# TopLevel.net
KiCad netlist of a schematic drawn in Altium Designer
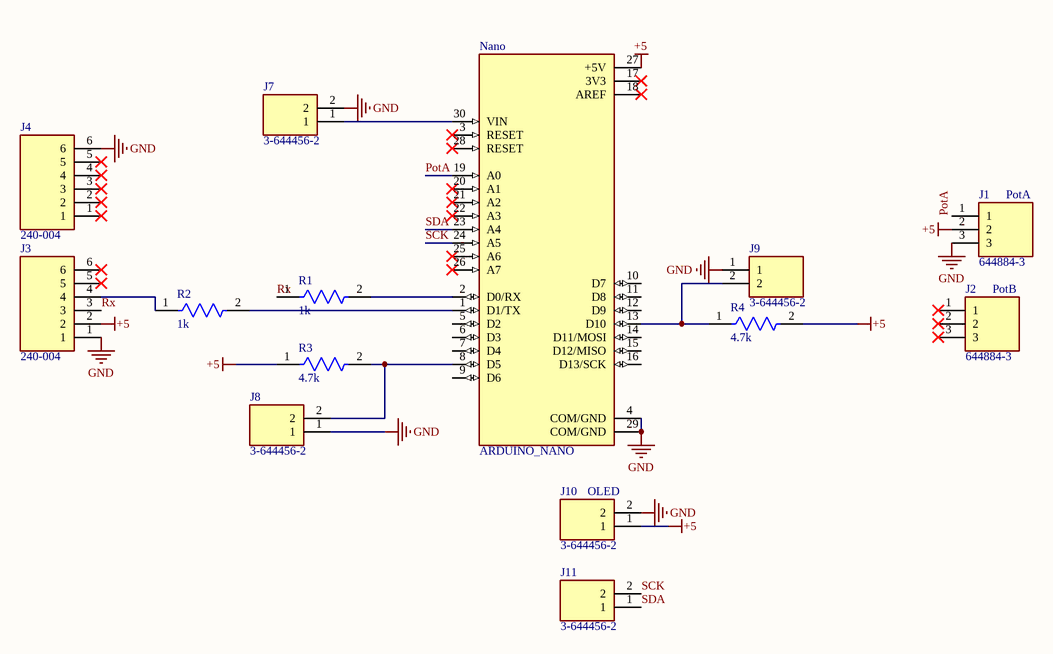
[diagram p0: TopLevel.SchDoc]

(export (version "E")
  (design (tool "Eeschema 10.0.6"))
  (components
    (comp (ref "J1")
      (value "644884-3")
      (footprint "TE_644884-3")
      (libsource (lib "Ryusei Kinosaki") (part "644884-3"))
    )
    (comp (ref "J2")
      (value "644884-3")
      (footprint "TE_644884-3")
      (libsource (lib "Ryusei Kinosaki") (part "644884-3"))
    )
    (comp (ref "J3")
      (value "240-004")
      (footprint "SamacSys:HDRV6W64P0X254_1X6_1524X254X909P")
      (description "Connector")
      (libsource (lib "*") (part "240-004"))
    )
    (comp (ref "J4")
      (value "240-004")
      (footprint "SamacSys:HDRV6W64P0X254_1X6_1524X254X909P")
      (description "Connector")
      (libsource (lib "*") (part "240-004"))
    )
    (comp (ref "J7")
      (value "3-644456-2")
      (footprint "TE_3-644456-2")
      (description "Connector Unshrouded Header HDR 2 Position 2.54mm Solder Straight Thru-Hole")
      (fields (field (name "MF") "TE Connectivity") (field (name "DIGI-KEY_PART_NUMBER") "A31112-ND"))
      (libsource (lib "") (part "3-644456-2_1"))
    )
    (comp (ref "J8")
      (value "3-644456-2")
      (footprint "TE_3-644456-2")
      (description "Connector Unshrouded Header HDR 2 Position 2.54mm Solder Straight Thru-Hole")
      (fields (field (name "MF") "TE Connectivity") (field (name "DIGI-KEY_PART_NUMBER") "A31112-ND"))
      (libsource (lib "") (part "3-644456-2_1"))
    )
    (comp (ref "J9")
      (value "3-644456-2")
      (footprint "TE_3-644456-2")
      (description "Connector Unshrouded Header HDR 2 Position 2.54mm Solder Straight Thru-Hole")
      (fields (field (name "MF") "TE Connectivity") (field (name "DIGI-KEY_PART_NUMBER") "A31112-ND"))
      (libsource (lib "Ryusei Kinosaki") (part "3-644456-2"))
    )
    (comp (ref "J10")
      (value "3-644456-2")
      (footprint "TE_3-644456-2")
      (description "Connector Unshrouded Header HDR 2 Position 2.54mm Solder Straight Thru-Hole")
      (fields (field (name "MF") "TE Connectivity") (field (name "DIGI-KEY_PART_NUMBER") "A31112-ND"))
      (libsource (lib "") (part "3-644456-2_1"))
    )
    (comp (ref "J11")
      (value "3-644456-2")
      (footprint "TE_3-644456-2")
      (description "Connector Unshrouded Header HDR 2 Position 2.54mm Solder Straight Thru-Hole")
      (fields (field (name "MF") "TE Connectivity") (field (name "DIGI-KEY_PART_NUMBER") "A31112-ND"))
      (libsource (lib "") (part "3-644456-2_1"))
    )
    (comp (ref "Nano")
      (value "ARDUINO_NANO")
      (footprint "SHIELD_ARDUINO_NANO")
      (description "Small, complete, and breadboard-friendly board based on the ATmega328 (Arduino Nano 3.x)")
      (fields (field (name "MF") "Arduino") (field (name "MP") "Arduino Nano"))
      (libsource (lib "Ryusei Kinosaki") (part "ARDUINO_NANO"))
    )
    (comp (ref "R1")
      (value "MRS25000C1001FCT00")
      (footprint "FP-MRS25-MFG")
      (description "RES 1K OHM 0.6W 1% AXIAL")
      (fields (field (name "TOLERANCE") "1%") (field (name "RESISTANCE") "1k"))
      (libsource (lib "Altium Content Vault") (part "1029c3af85768c4190bb7ad29bc67b5"))
    )
    (comp (ref "R2")
      (value "MRS25000C1001FCT00")
      (footprint "FP-MRS25-MFG")
      (description "RES 1K OHM 0.6W 1% AXIAL")
      (fields (field (name "TOLERANCE") "1%") (field (name "RESISTANCE") "1k"))
      (libsource (lib "Altium Content Vault") (part "1029c3af85768c4190bb7ad29bc67b5"))
    )
    (comp (ref "R3")
      (value "MRS25000C1001FCT00")
      (footprint "FP-MRS25-MFG")
      (description "RES 1K OHM 0.6W 1% AXIAL")
      (fields (field (name "TOLERANCE") "1%") (field (name "RESISTANCE") "4.7k"))
      (libsource (lib "Altium Content Vault") (part "1029c3af85768c4190bb7ad29bc67b5"))
    )
    (comp (ref "R4")
      (value "MRS25000C1001FCT00")
      (footprint "FP-MRS25-MFG")
      (description "RES 1K OHM 0.6W 1% AXIAL")
      (fields (field (name "TOLERANCE") "1%") (field (name "RESISTANCE") "4.7k"))
      (libsource (lib "Altium Content Vault") (part "1029c3af85768c4190bb7ad29bc67b5"))
    )
  )
  (nets
    (net (code "1") (name "+5") (class "Default")
      (node (ref "J1") (pin "2") (pinfunction "2_2") (pintype "passive"))
      (node (ref "J10") (pin "1") (pinfunction "1_1") (pintype "passive"))
      (node (ref "J3") (pin "2") (pinfunction "2_2") (pintype "passive"))
      (node (ref "Nano") (pin "27") (pinfunction "+5V_27") (pintype "power_in"))
      (node (ref "R3") (pin "1") (pinfunction "1_1") (pintype "passive"))
      (node (ref "R4") (pin "2") (pinfunction "2_2") (pintype "passive"))
    )
    (net (code "2") (name "/PotA") (class "Default")
      (node (ref "J1") (pin "1") (pinfunction "1_1") (pintype "passive"))
      (node (ref "Nano") (pin "19") (pinfunction "A0_19") (pintype "input"))
    )
    (net (code "3") (name "/Rx") (class "Default")
      (node (ref "J3") (pin "3") (pinfunction "3_3") (pintype "passive"))
      (node (ref "R1") (pin "1") (pinfunction "1_1") (pintype "passive"))
    )
    (net (code "4") (name "/SCK") (class "Default")
      (node (ref "J11") (pin "2") (pinfunction "2_2") (pintype "passive"))
      (node (ref "Nano") (pin "24") (pinfunction "A5_24") (pintype "input"))
    )
    (net (code "5") (name "/SDA") (class "Default")
      (node (ref "J11") (pin "1") (pinfunction "1_1") (pintype "passive"))
      (node (ref "Nano") (pin "23") (pinfunction "A4_23") (pintype "input"))
    )
    (net (code "6") (name "GND") (class "Default")
      (node (ref "J1") (pin "3") (pinfunction "3_3") (pintype "passive"))
      (node (ref "J10") (pin "2") (pinfunction "2_2") (pintype "passive"))
      (node (ref "J3") (pin "1") (pinfunction "1_1") (pintype "passive"))
      (node (ref "J4") (pin "6") (pinfunction "6_6") (pintype "passive"))
      (node (ref "J7") (pin "2") (pinfunction "2_2") (pintype "passive"))
      (node (ref "J8") (pin "1") (pinfunction "1_1") (pintype "passive"))
      (node (ref "J9") (pin "1") (pinfunction "1_1") (pintype "passive"))
      (node (ref "Nano") (pin "29") (pinfunction "COM/GND_29") (pintype "power_in"))
      (node (ref "Nano") (pin "4") (pinfunction "COM/GND_4") (pintype "power_in"))
    )
    (net (code "7") (name "Net-(J3-Pad4)") (class "Default")
      (node (ref "J3") (pin "4") (pinfunction "4_4") (pintype "passive"))
      (node (ref "R2") (pin "1") (pinfunction "1_1") (pintype "passive"))
    )
    (net (code "8") (name "Net-(Nano-D0{slash}RX)") (class "Default")
      (node (ref "Nano") (pin "2") (pinfunction "D0/RX_2") (pintype "bidirectional"))
      (node (ref "R1") (pin "2") (pinfunction "2_2") (pintype "passive"))
    )
    (net (code "9") (name "Net-(Nano-D1{slash}TX)") (class "Default")
      (node (ref "Nano") (pin "1") (pinfunction "D1/TX_1") (pintype "bidirectional"))
      (node (ref "R2") (pin "2") (pinfunction "2_2") (pintype "passive"))
    )
    (net (code "10") (name "Net-(Nano-D5)") (class "Default")
      (node (ref "J8") (pin "2") (pinfunction "2_2") (pintype "passive"))
      (node (ref "Nano") (pin "8") (pinfunction "D5_8") (pintype "bidirectional"))
      (node (ref "R3") (pin "2") (pinfunction "2_2") (pintype "passive"))
    )
    (net (code "11") (name "Net-(Nano-D10)") (class "Default")
      (node (ref "J9") (pin "2") (pinfunction "2_2") (pintype "passive"))
      (node (ref "Nano") (pin "13") (pinfunction "D10_13") (pintype "bidirectional"))
      (node (ref "R4") (pin "1") (pinfunction "1_1") (pintype "passive"))
    )
    (net (code "12") (name "Net-(Nano-VIN)") (class "Default")
      (node (ref "J7") (pin "1") (pinfunction "1_1") (pintype "passive"))
      (node (ref "Nano") (pin "30") (pinfunction "VIN_30") (pintype "input"))
    )
    (net (code "13") (name "unconnected-(J2-Pad1)") (class "Default")
      (node (ref "J2") (pin "1") (pinfunction "1_1") (pintype "passive+no_connect"))
    )
    (net (code "14") (name "unconnected-(J2-Pad2)") (class "Default")
      (node (ref "J2") (pin "2") (pinfunction "2_2") (pintype "passive+no_connect"))
    )
    (net (code "15") (name "unconnected-(J2-Pad3)") (class "Default")
      (node (ref "J2") (pin "3") (pinfunction "3_3") (pintype "passive+no_connect"))
    )
    (net (code "16") (name "unconnected-(J3-Pad5)") (class "Default")
      (node (ref "J3") (pin "5") (pinfunction "5_5") (pintype "passive+no_connect"))
    )
    (net (code "17") (name "unconnected-(J3-Pad6)") (class "Default")
      (node (ref "J3") (pin "6") (pinfunction "6_6") (pintype "passive+no_connect"))
    )
    (net (code "18") (name "unconnected-(J4-Pad1)") (class "Default")
      (node (ref "J4") (pin "1") (pinfunction "1_1") (pintype "passive+no_connect"))
    )
    (net (code "19") (name "unconnected-(J4-Pad2)") (class "Default")
      (node (ref "J4") (pin "2") (pinfunction "2_2") (pintype "passive+no_connect"))
    )
    (net (code "20") (name "unconnected-(J4-Pad3)") (class "Default")
      (node (ref "J4") (pin "3") (pinfunction "3_3") (pintype "passive+no_connect"))
    )
    (net (code "21") (name "unconnected-(J4-Pad4)") (class "Default")
      (node (ref "J4") (pin "4") (pinfunction "4_4") (pintype "passive+no_connect"))
    )
    (net (code "22") (name "unconnected-(J4-Pad5)") (class "Default")
      (node (ref "J4") (pin "5") (pinfunction "5_5") (pintype "passive+no_connect"))
    )
    (net (code "23") (name "unconnected-(Nano-3V3-Pad17)") (class "Default")
      (node (ref "Nano") (pin "17") (pinfunction "3V3_17") (pintype "power_in+no_connect"))
    )
    (net (code "24") (name "unconnected-(Nano-A1-Pad20)") (class "Default")
      (node (ref "Nano") (pin "20") (pinfunction "A1_20") (pintype "input+no_connect"))
    )
    (net (code "25") (name "unconnected-(Nano-A2-Pad21)") (class "Default")
      (node (ref "Nano") (pin "21") (pinfunction "A2_21") (pintype "input+no_connect"))
    )
    (net (code "26") (name "unconnected-(Nano-A3-Pad22)") (class "Default")
      (node (ref "Nano") (pin "22") (pinfunction "A3_22") (pintype "input+no_connect"))
    )
    (net (code "27") (name "unconnected-(Nano-A6-Pad25)") (class "Default")
      (node (ref "Nano") (pin "25") (pinfunction "A6_25") (pintype "input+no_connect"))
    )
    (net (code "28") (name "unconnected-(Nano-A7-Pad26)") (class "Default")
      (node (ref "Nano") (pin "26") (pinfunction "A7_26") (pintype "input+no_connect"))
    )
    (net (code "29") (name "unconnected-(Nano-AREF-Pad18)") (class "Default")
      (node (ref "Nano") (pin "18") (pinfunction "AREF_18") (pintype "power_in+no_connect"))
    )
    (net (code "30") (name "unconnected-(Nano-D2-Pad5)") (class "Default")
      (node (ref "Nano") (pin "5") (pinfunction "D2_5") (pintype "bidirectional"))
    )
    (net (code "31") (name "unconnected-(Nano-D3-Pad6)") (class "Default")
      (node (ref "Nano") (pin "6") (pinfunction "D3_6") (pintype "bidirectional"))
    )
    (net (code "32") (name "unconnected-(Nano-D4-Pad7)") (class "Default")
      (node (ref "Nano") (pin "7") (pinfunction "D4_7") (pintype "bidirectional"))
    )
    (net (code "33") (name "unconnected-(Nano-D6-Pad9)") (class "Default")
      (node (ref "Nano") (pin "9") (pinfunction "D6_9") (pintype "bidirectional"))
    )
    (net (code "34") (name "unconnected-(Nano-D7-Pad10)") (class "Default")
      (node (ref "Nano") (pin "10") (pinfunction "D7_10") (pintype "bidirectional"))
    )
    (net (code "35") (name "unconnected-(Nano-D8-Pad11)") (class "Default")
      (node (ref "Nano") (pin "11") (pinfunction "D8_11") (pintype "bidirectional"))
    )
    (net (code "36") (name "unconnected-(Nano-D9-Pad12)") (class "Default")
      (node (ref "Nano") (pin "12") (pinfunction "D9_12") (pintype "bidirectional"))
    )
    (net (code "37") (name "unconnected-(Nano-D11{slash}MOSI-Pad14)") (class "Default")
      (node (ref "Nano") (pin "14") (pinfunction "D11/MOSI_14") (pintype "bidirectional"))
    )
    (net (code "38") (name "unconnected-(Nano-D12{slash}MISO-Pad15)") (class "Default")
      (node (ref "Nano") (pin "15") (pinfunction "D12/MISO_15") (pintype "bidirectional"))
    )
    (net (code "39") (name "unconnected-(Nano-D13{slash}SCK-Pad16)") (class "Default")
      (node (ref "Nano") (pin "16") (pinfunction "D13/SCK_16") (pintype "bidirectional"))
    )
    (net (code "40") (name "unconnected-(Nano-RESET-Pad3)") (class "Default")
      (node (ref "Nano") (pin "3") (pinfunction "RESET_3") (pintype "input+no_connect"))
    )
    (net (code "41") (name "unconnected-(Nano-RESET-Pad28)") (class "Default")
      (node (ref "Nano") (pin "28") (pinfunction "RESET_28") (pintype "input+no_connect"))
    )
  )
)
